# ALIM.net
KiCad netlist of a schematic drawn in EAGLE
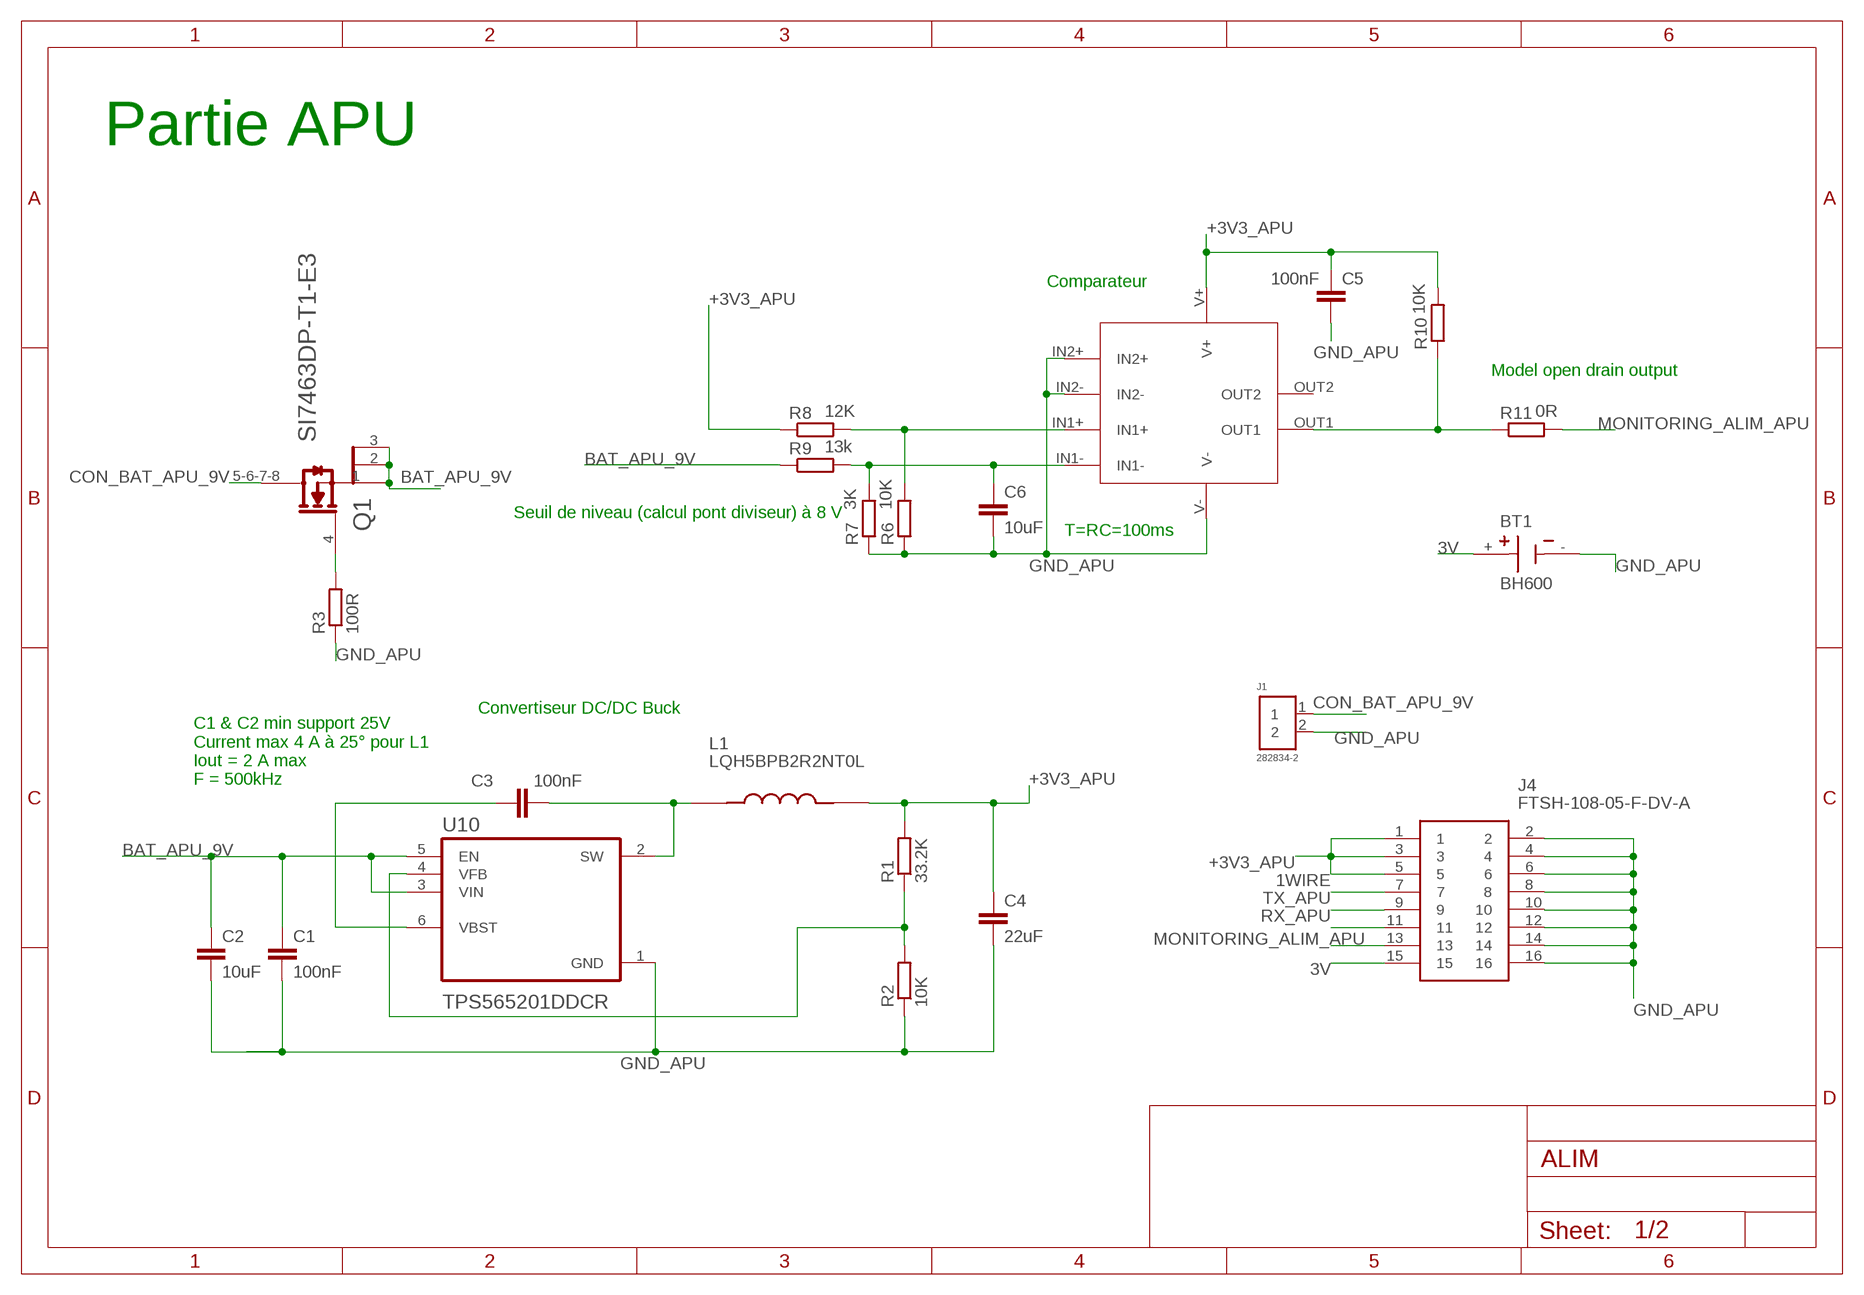
[diagram p0: schematic, sheet 1]
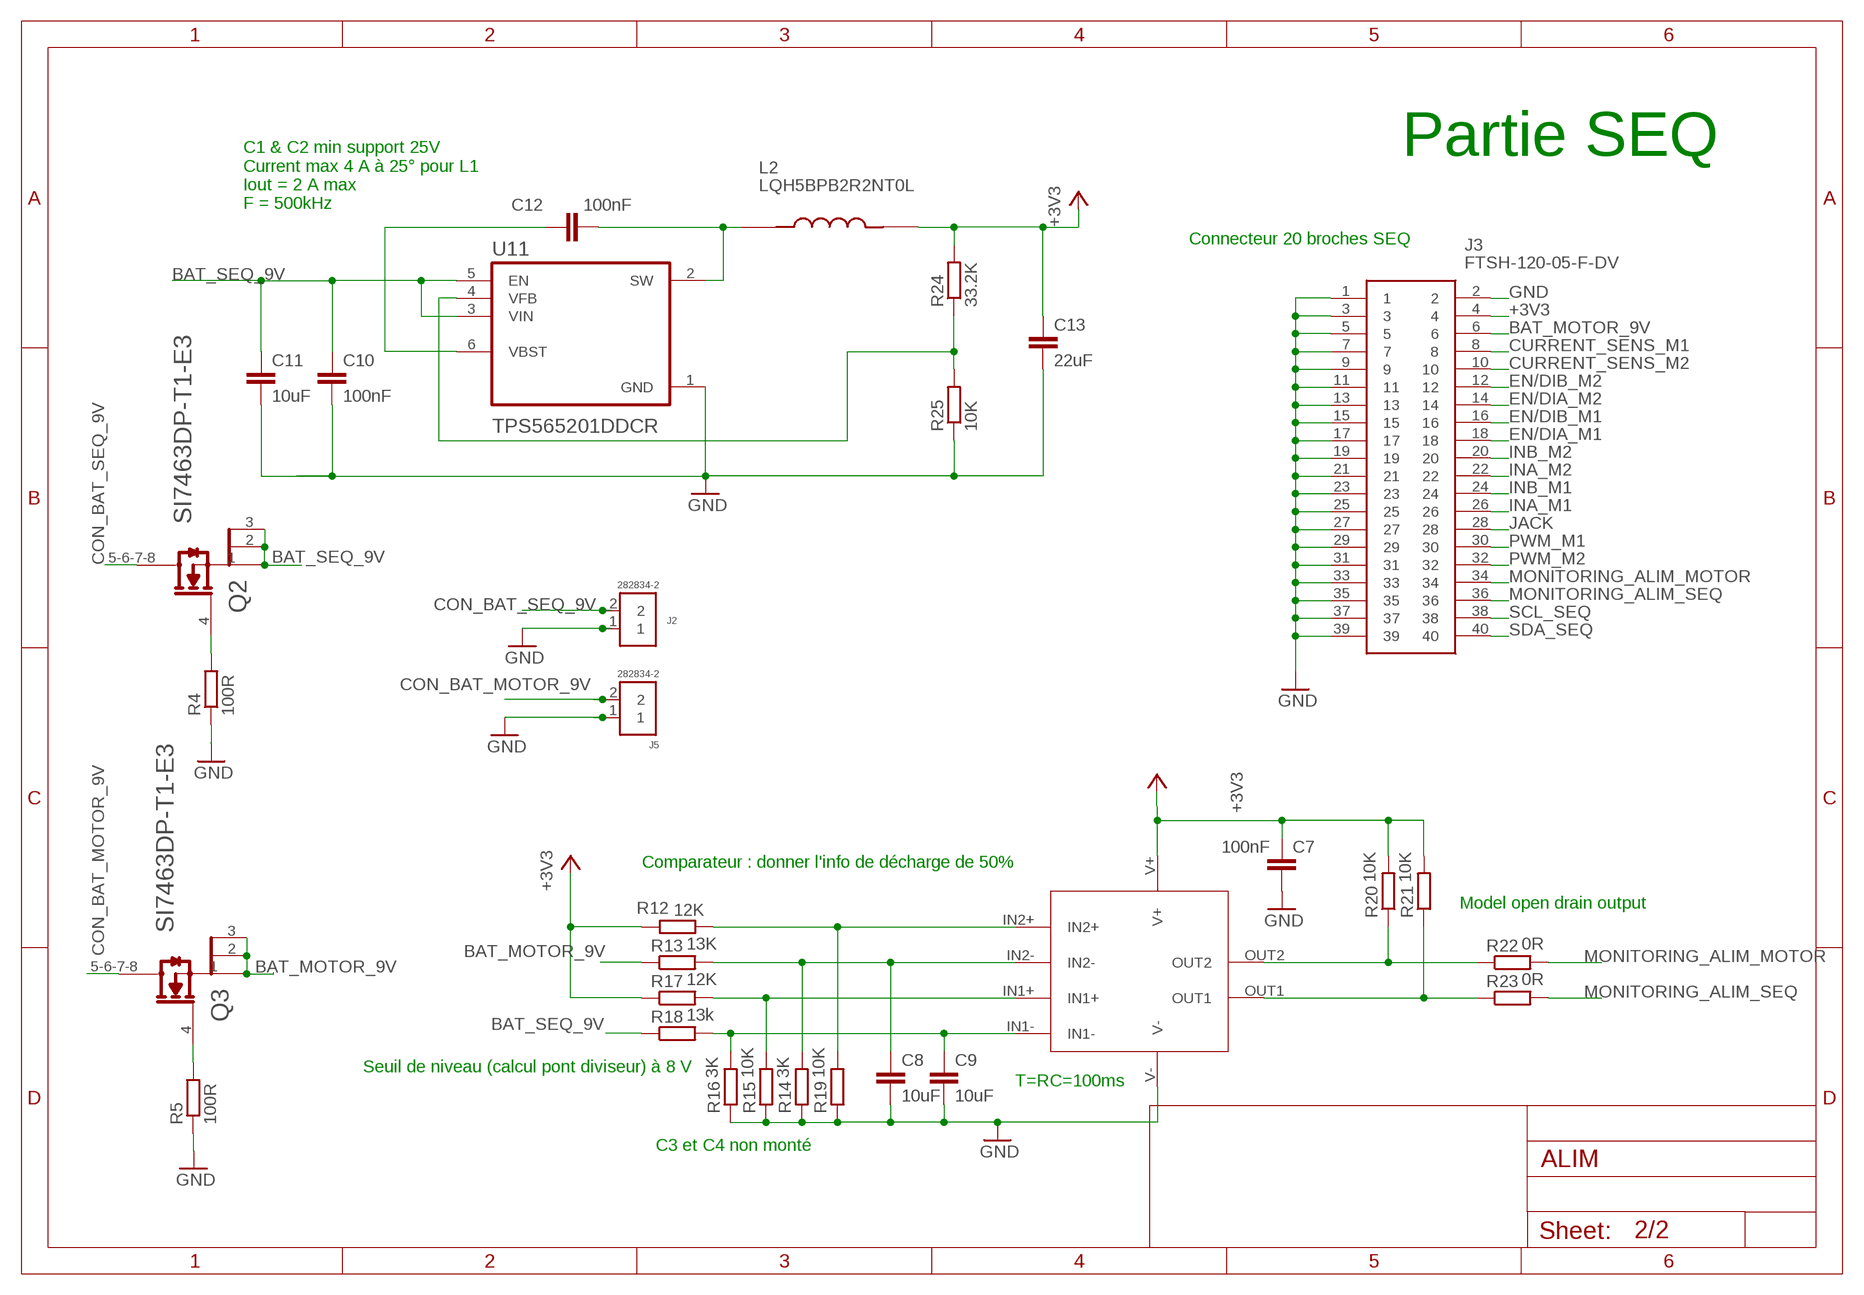
[diagram p1: schematic, sheet 2]

(export (version "E")
  (design (tool "Eeschema 10.0.6"))
  (components
    (comp (ref "BT1")
      (value "BH600")
      (footprint "eagle-import:BAT_BH600")
      (fields (field (name "MF") "MPD (Memory"))
      (libsource (lib "eagle-import") (part "BH600"))
    )
    (comp (ref "C1")
      (value "100nF")
      (footprint "eagle-import:C0805")
      (libsource (lib "eagle-import") (part "C-EUC0805"))
    )
    (comp (ref "C2")
      (value "10uF")
      (footprint "eagle-import:C0805")
      (libsource (lib "eagle-import") (part "C-EUC0805"))
    )
    (comp (ref "C3")
      (value "100nF")
      (footprint "eagle-import:C0805")
      (libsource (lib "eagle-import") (part "C-EUC0805"))
    )
    (comp (ref "C4")
      (value "22uF")
      (footprint "eagle-import:C0805")
      (libsource (lib "eagle-import") (part "C-EUC0805"))
    )
    (comp (ref "C5")
      (value "100nF")
      (footprint "eagle-import:C0805")
      (libsource (lib "eagle-import") (part "C-EUC0805"))
    )
    (comp (ref "C6")
      (value "10uF")
      (footprint "eagle-import:C0805")
      (libsource (lib "eagle-import") (part "C-EUC0805"))
    )
    (comp (ref "J1")
      (value "282834-2")
      (footprint "eagle-import:CONN_282834-2")
      (fields (field (name "MF") "TE Connectivity"))
      (libsource (lib "eagle-import") (part "282834-2"))
    )
    (comp (ref "J4")
      (value "FTSH-108-05-F-DV-A")
      (footprint "eagle-import:FTSH-108-XX-YYY-DV-A")
      (fields (field (name "MOUSER_PART_NUMBER") "200-FTSH10805FDVA"))
      (libsource (lib "eagle-import") (part "FTSH-108-05-F-DV-A"))
    )
    (comp (ref "L1")
      (value "LQH5BPB2R2NT0L")
      (footprint "eagle-import:IND_LQH5BPB2R2NT0L")
      (fields (field (name "MF") "Murata"))
      (libsource (lib "eagle-import") (part "LQH5BPB2R2NT0L"))
    )
    (comp (ref "Q1")
      (value "VISHAY_SI7463DP-T1-E3VISHAY_SI7463DP-T1-E3_0_0")
      (footprint "eagle-import:VISHAY_SI7463DP-T1-E3_0")
      (fields
        (field (name "DIGIKEY_PART_NUMBER") "SI7463DP-T1-E3CT-ND")
        (field (name "MF") "Vishay")
        (field (name "MOUSER_PART_NUMBER") "781-SI7463DP-T1-E3")
      )
      (libsource (lib "eagle-import") (part "VISHAY_SI7463DP-T1-E3VISHAY_SI7463DP-T1-E3_0_0"))
    )
    (comp (ref "R1")
      (value "33.2K")
      (footprint "eagle-import:R0603")
      (libsource (lib "eagle-import") (part "R-EU_R0603"))
    )
    (comp (ref "R2")
      (value "10K")
      (footprint "eagle-import:R0603")
      (libsource (lib "eagle-import") (part "R-EU_R0603"))
    )
    (comp (ref "R3")
      (value "100R")
      (footprint "eagle-import:R0603")
      (libsource (lib "eagle-import") (part "R-EU_R0603"))
    )
    (comp (ref "R6")
      (value "10K")
      (footprint "eagle-import:R0603")
      (libsource (lib "eagle-import") (part "R-EU_R0603"))
    )
    (comp (ref "R7")
      (value "3K")
      (footprint "eagle-import:R0603")
      (libsource (lib "eagle-import") (part "R-EU_R0603"))
    )
    (comp (ref "R8")
      (value "12K")
      (footprint "eagle-import:R0603")
      (libsource (lib "eagle-import") (part "R-EU_R0603"))
    )
    (comp (ref "R9")
      (value "13k")
      (footprint "eagle-import:R0603")
      (libsource (lib "eagle-import") (part "R-EU_R0603"))
    )
    (comp (ref "R10")
      (value "10K")
      (footprint "eagle-import:R0603")
      (libsource (lib "eagle-import") (part "R-EU_R0603"))
    )
    (comp (ref "R11")
      (value "0R")
      (footprint "eagle-import:R0603")
      (libsource (lib "eagle-import") (part "R-EU_R0603"))
    )
    (comp (ref "TLV1")
      (value "TLV9022")
      (footprint "eagle-import:TLV9022")
      (libsource (lib "eagle-import") (part "TLV9022"))
    )
    (comp (ref "U10")
      (value "TPS565201DDCR")
      (footprint "eagle-import:SOT95P280X110-6N")
      (fields (field (name "MF") "Texas Instruments"))
      (libsource (lib "eagle-import") (part "TPS565201DDCR"))
    )
    (comp (ref "C7")
      (value "100nF")
      (footprint "eagle-import:C0805")
      (libsource (lib "eagle-import") (part "C-EUC0805"))
    )
    (comp (ref "C8")
      (value "10uF")
      (footprint "eagle-import:C0805")
      (libsource (lib "eagle-import") (part "C-EUC0805"))
    )
    (comp (ref "C9")
      (value "10uF")
      (footprint "eagle-import:C0805")
      (libsource (lib "eagle-import") (part "C-EUC0805"))
    )
    (comp (ref "C10")
      (value "100nF")
      (footprint "eagle-import:C0805")
      (libsource (lib "eagle-import") (part "C-EUC0805"))
    )
    (comp (ref "C11")
      (value "10uF")
      (footprint "eagle-import:C0805")
      (libsource (lib "eagle-import") (part "C-EUC0805"))
    )
    (comp (ref "C12")
      (value "100nF")
      (footprint "eagle-import:C0805")
      (libsource (lib "eagle-import") (part "C-EUC0805"))
    )
    (comp (ref "C13")
      (value "22uF")
      (footprint "eagle-import:C0805")
      (libsource (lib "eagle-import") (part "C-EUC0805"))
    )
    (comp (ref "J2")
      (value "282834-2")
      (footprint "eagle-import:CONN_282834-2")
      (fields (field (name "MF") "TE Connectivity"))
      (libsource (lib "eagle-import") (part "282834-2"))
    )
    (comp (ref "J3")
      (value "FTSH-120-05-F-DV")
      (footprint "eagle-import:FTSH-120-XX-YYY-DV")
      (libsource (lib "eagle-import") (part "FTSH-120-05-F-DV"))
    )
    (comp (ref "J5")
      (value "282834-2")
      (footprint "eagle-import:CONN_282834-2")
      (fields (field (name "MF") "TE Connectivity"))
      (libsource (lib "eagle-import") (part "282834-2"))
    )
    (comp (ref "L2")
      (value "LQH5BPB2R2NT0L")
      (footprint "eagle-import:IND_LQH5BPB2R2NT0L")
      (fields (field (name "MF") "Murata"))
      (libsource (lib "eagle-import") (part "LQH5BPB2R2NT0L"))
    )
    (comp (ref "Q2")
      (value "VISHAY_SI7463DP-T1-E3VISHAY_SI7463DP-T1-E3_0_0")
      (footprint "eagle-import:VISHAY_SI7463DP-T1-E3_0")
      (fields
        (field (name "DIGIKEY_PART_NUMBER") "SI7463DP-T1-E3CT-ND")
        (field (name "MF") "Vishay")
        (field (name "MOUSER_PART_NUMBER") "781-SI7463DP-T1-E3")
      )
      (libsource (lib "eagle-import") (part "VISHAY_SI7463DP-T1-E3VISHAY_SI7463DP-T1-E3_0_0"))
    )
    (comp (ref "Q3")
      (value "VISHAY_SI7463DP-T1-E3VISHAY_SI7463DP-T1-E3_0_0")
      (footprint "eagle-import:VISHAY_SI7463DP-T1-E3_0")
      (fields
        (field (name "DIGIKEY_PART_NUMBER") "SI7463DP-T1-E3CT-ND")
        (field (name "MF") "Vishay")
        (field (name "MOUSER_PART_NUMBER") "781-SI7463DP-T1-E3")
      )
      (libsource (lib "eagle-import") (part "VISHAY_SI7463DP-T1-E3VISHAY_SI7463DP-T1-E3_0_0"))
    )
    (comp (ref "R4")
      (value "100R")
      (footprint "eagle-import:R0603")
      (libsource (lib "eagle-import") (part "R-EU_R0603"))
    )
    (comp (ref "R5")
      (value "100R")
      (footprint "eagle-import:R0603")
      (libsource (lib "eagle-import") (part "R-EU_R0603"))
    )
    (comp (ref "R12")
      (value "12K")
      (footprint "eagle-import:R0603")
      (libsource (lib "eagle-import") (part "R-EU_R0603"))
    )
    (comp (ref "R13")
      (value "13K")
      (footprint "eagle-import:R0603")
      (libsource (lib "eagle-import") (part "R-EU_R0603"))
    )
    (comp (ref "R14")
      (value "3K")
      (footprint "eagle-import:R0603")
      (libsource (lib "eagle-import") (part "R-EU_R0603"))
    )
    (comp (ref "R15")
      (value "10K")
      (footprint "eagle-import:R0603")
      (libsource (lib "eagle-import") (part "R-EU_R0603"))
    )
    (comp (ref "R16")
      (value "3K")
      (footprint "eagle-import:R0603")
      (libsource (lib "eagle-import") (part "R-EU_R0603"))
    )
    (comp (ref "R17")
      (value "12K")
      (footprint "eagle-import:R0603")
      (libsource (lib "eagle-import") (part "R-EU_R0603"))
    )
    (comp (ref "R18")
      (value "13k")
      (footprint "eagle-import:R0603")
      (libsource (lib "eagle-import") (part "R-EU_R0603"))
    )
    (comp (ref "R19")
      (value "10K")
      (footprint "eagle-import:R0603")
      (libsource (lib "eagle-import") (part "R-EU_R0603"))
    )
    (comp (ref "R20")
      (value "10K")
      (footprint "eagle-import:R0603")
      (libsource (lib "eagle-import") (part "R-EU_R0603"))
    )
    (comp (ref "R21")
      (value "10K")
      (footprint "eagle-import:R0603")
      (libsource (lib "eagle-import") (part "R-EU_R0603"))
    )
    (comp (ref "R22")
      (value "0R")
      (footprint "eagle-import:R0603")
      (libsource (lib "eagle-import") (part "R-EU_R0603"))
    )
    (comp (ref "R23")
      (value "0R")
      (footprint "eagle-import:R0603")
      (libsource (lib "eagle-import") (part "R-EU_R0603"))
    )
    (comp (ref "R24")
      (value "33.2K")
      (footprint "eagle-import:R0603")
      (libsource (lib "eagle-import") (part "R-EU_R0603"))
    )
    (comp (ref "R25")
      (value "10K")
      (footprint "eagle-import:R0603")
      (libsource (lib "eagle-import") (part "R-EU_R0603"))
    )
    (comp (ref "TLV2")
      (value "TLV9022")
      (footprint "eagle-import:TLV9022")
      (libsource (lib "eagle-import") (part "TLV9022"))
    )
    (comp (ref "U11")
      (value "TPS565201DDCR")
      (footprint "eagle-import:SOT95P280X110-6N")
      (fields (field (name "MF") "Texas Instruments"))
      (libsource (lib "eagle-import") (part "TPS565201DDCR"))
    )
  )
  (nets
    (net (code "1") (name "+3V3") (class "Default")
      (node (ref "C13") (pin "1") (pinfunction "1_1") (pintype "passive"))
      (node (ref "C7") (pin "1") (pinfunction "1_1") (pintype "passive"))
      (node (ref "J3") (pin "4") (pinfunction "4_4") (pintype "bidirectional"))
      (node (ref "L2") (pin "2") (pinfunction "2_2") (pintype "passive"))
      (node (ref "R12") (pin "2") (pinfunction "2_2") (pintype "passive"))
      (node (ref "R17") (pin "1") (pinfunction "1_1") (pintype "passive"))
      (node (ref "R20") (pin "2") (pinfunction "2_2") (pintype "passive"))
      (node (ref "R21") (pin "2") (pinfunction "2_2") (pintype "passive"))
      (node (ref "R24") (pin "2") (pinfunction "2_2") (pintype "passive"))
      (node (ref "TLV2") (pin "V+") (pinfunction "V+_V+") (pintype "bidirectional"))
    )
    (net (code "2") (name "+3V3_APU") (class "Default")
      (node (ref "C4") (pin "1") (pinfunction "1_1") (pintype "passive"))
      (node (ref "C5") (pin "1") (pinfunction "1_1") (pintype "passive"))
      (node (ref "J4") (pin "1") (pinfunction "1_1") (pintype "bidirectional"))
      (node (ref "J4") (pin "3") (pinfunction "3_3") (pintype "bidirectional"))
      (node (ref "J4") (pin "5") (pinfunction "5_5") (pintype "bidirectional"))
      (node (ref "L1") (pin "2") (pinfunction "2_2") (pintype "passive"))
      (node (ref "R1") (pin "2") (pinfunction "2_2") (pintype "passive"))
      (node (ref "R10") (pin "2") (pinfunction "2_2") (pintype "passive"))
      (node (ref "R8") (pin "1") (pinfunction "1_1") (pintype "passive"))
      (node (ref "TLV1") (pin "V+") (pinfunction "V+_V+") (pintype "bidirectional"))
    )
    (net (code "3") (name "1WIRE") (class "Default")
      (node (ref "J4") (pin "7") (pinfunction "7_7") (pintype "bidirectional"))
    )
    (net (code "4") (name "3V") (class "Default")
      (node (ref "BT1") (pin "+") (pinfunction "+_+") (pintype "passive"))
      (node (ref "J4") (pin "15") (pinfunction "15_15") (pintype "bidirectional"))
    )
    (net (code "5") (name "BAT_APU_9V") (class "Default")
      (node (ref "C1") (pin "1") (pinfunction "1_1") (pintype "passive"))
      (node (ref "C2") (pin "1") (pinfunction "1_1") (pintype "passive"))
      (node (ref "Q1") (pin "1") (pinfunction "1_S_1") (pintype "passive"))
      (node (ref "Q1") (pin "2") (pinfunction "2_S_2") (pintype "passive"))
      (node (ref "Q1") (pin "3") (pinfunction "3_S_3") (pintype "passive"))
      (node (ref "R9") (pin "1") (pinfunction "1_1") (pintype "passive"))
      (node (ref "U10") (pin "3") (pinfunction "VIN_3") (pintype "input"))
      (node (ref "U10") (pin "5") (pinfunction "EN_5") (pintype "input"))
    )
    (net (code "6") (name "BAT_MOTOR_9V") (class "Default")
      (node (ref "J3") (pin "6") (pinfunction "6_6") (pintype "bidirectional"))
      (node (ref "Q3") (pin "1") (pinfunction "1_S_1") (pintype "passive"))
      (node (ref "Q3") (pin "2") (pinfunction "2_S_2") (pintype "passive"))
      (node (ref "Q3") (pin "3") (pinfunction "3_S_3") (pintype "passive"))
      (node (ref "R13") (pin "1") (pinfunction "1_1") (pintype "passive"))
    )
    (net (code "7") (name "BAT_SEQ_9V") (class "Default")
      (node (ref "C10") (pin "1") (pinfunction "1_1") (pintype "passive"))
      (node (ref "C11") (pin "1") (pinfunction "1_1") (pintype "passive"))
      (node (ref "Q2") (pin "1") (pinfunction "1_S_1") (pintype "passive"))
      (node (ref "Q2") (pin "2") (pinfunction "2_S_2") (pintype "passive"))
      (node (ref "Q2") (pin "3") (pinfunction "3_S_3") (pintype "passive"))
      (node (ref "R18") (pin "1") (pinfunction "1_1") (pintype "passive"))
      (node (ref "U11") (pin "3") (pinfunction "VIN_3") (pintype "input"))
      (node (ref "U11") (pin "5") (pinfunction "EN_5") (pintype "input"))
    )
    (net (code "8") (name "CON_BAT_APU_9V") (class "Default")
      (node (ref "J1") (pin "1") (pinfunction "1_1") (pintype "passive"))
      (node (ref "Q1") (pin "5-6-7-8") (pinfunction "D_5-6-7-8") (pintype "passive"))
    )
    (net (code "9") (name "CON_BAT_MOTOR_9V") (class "Default")
      (node (ref "J5") (pin "2") (pinfunction "2_2") (pintype "passive"))
      (node (ref "Q3") (pin "5-6-7-8") (pinfunction "D_5-6-7-8") (pintype "passive"))
    )
    (net (code "10") (name "CON_BAT_SEQ_9V") (class "Default")
      (node (ref "J2") (pin "2") (pinfunction "2_2") (pintype "passive"))
      (node (ref "Q2") (pin "5-6-7-8") (pinfunction "D_5-6-7-8") (pintype "passive"))
    )
    (net (code "11") (name "CURRENT_SENS_M1") (class "Default")
      (node (ref "J3") (pin "8") (pinfunction "8_8") (pintype "bidirectional"))
    )
    (net (code "12") (name "CURRENT_SENS_M2") (class "Default")
      (node (ref "J3") (pin "10") (pinfunction "10_10") (pintype "bidirectional"))
    )
    (net (code "13") (name "EN{slash}DIA_M1") (class "Default")
      (node (ref "J3") (pin "18") (pinfunction "18_18") (pintype "bidirectional"))
    )
    (net (code "14") (name "EN{slash}DIA_M2") (class "Default")
      (node (ref "J3") (pin "14") (pinfunction "14_14") (pintype "bidirectional"))
    )
    (net (code "15") (name "EN{slash}DIB_M1") (class "Default")
      (node (ref "J3") (pin "16") (pinfunction "16_16") (pintype "bidirectional"))
    )
    (net (code "16") (name "EN{slash}DIB_M2") (class "Default")
      (node (ref "J3") (pin "12") (pinfunction "12_12") (pintype "bidirectional"))
    )
    (net (code "17") (name "GND") (class "Default")
      (node (ref "C10") (pin "2") (pinfunction "2_2") (pintype "passive"))
      (node (ref "C11") (pin "2") (pinfunction "2_2") (pintype "passive"))
      (node (ref "C13") (pin "2") (pinfunction "2_2") (pintype "passive"))
      (node (ref "C7") (pin "2") (pinfunction "2_2") (pintype "passive"))
      (node (ref "C8") (pin "2") (pinfunction "2_2") (pintype "passive"))
      (node (ref "C9") (pin "2") (pinfunction "2_2") (pintype "passive"))
      (node (ref "J2") (pin "1") (pinfunction "1_1") (pintype "passive"))
      (node (ref "J3") (pin "1") (pinfunction "1_1") (pintype "bidirectional"))
      (node (ref "J3") (pin "11") (pinfunction "11_11") (pintype "bidirectional"))
      (node (ref "J3") (pin "13") (pinfunction "13_13") (pintype "bidirectional"))
      (node (ref "J3") (pin "15") (pinfunction "15_15") (pintype "bidirectional"))
      (node (ref "J3") (pin "17") (pinfunction "17_17") (pintype "bidirectional"))
      (node (ref "J3") (pin "19") (pinfunction "19_19") (pintype "bidirectional"))
      (node (ref "J3") (pin "2") (pinfunction "2_2") (pintype "bidirectional"))
      (node (ref "J3") (pin "21") (pinfunction "21_21") (pintype "bidirectional"))
      (node (ref "J3") (pin "23") (pinfunction "23_23") (pintype "bidirectional"))
      (node (ref "J3") (pin "25") (pinfunction "25_25") (pintype "bidirectional"))
      (node (ref "J3") (pin "27") (pinfunction "27_27") (pintype "bidirectional"))
      (node (ref "J3") (pin "29") (pinfunction "29_29") (pintype "bidirectional"))
      (node (ref "J3") (pin "3") (pinfunction "3_3") (pintype "bidirectional"))
      (node (ref "J3") (pin "31") (pinfunction "31_31") (pintype "bidirectional"))
      (node (ref "J3") (pin "33") (pinfunction "33_33") (pintype "bidirectional"))
      (node (ref "J3") (pin "35") (pinfunction "35_35") (pintype "bidirectional"))
      (node (ref "J3") (pin "37") (pinfunction "37_37") (pintype "bidirectional"))
      (node (ref "J3") (pin "39") (pinfunction "39_39") (pintype "bidirectional"))
      (node (ref "J3") (pin "5") (pinfunction "5_5") (pintype "bidirectional"))
      (node (ref "J3") (pin "7") (pinfunction "7_7") (pintype "bidirectional"))
      (node (ref "J3") (pin "9") (pinfunction "9_9") (pintype "bidirectional"))
      (node (ref "J5") (pin "1") (pinfunction "1_1") (pintype "passive"))
      (node (ref "R14") (pin "1") (pinfunction "1_1") (pintype "passive"))
      (node (ref "R15") (pin "1") (pinfunction "1_1") (pintype "passive"))
      (node (ref "R16") (pin "1") (pinfunction "1_1") (pintype "passive"))
      (node (ref "R19") (pin "1") (pinfunction "1_1") (pintype "passive"))
      (node (ref "R25") (pin "1") (pinfunction "1_1") (pintype "passive"))
      (node (ref "R4") (pin "1") (pinfunction "1_1") (pintype "passive"))
      (node (ref "R5") (pin "1") (pinfunction "1_1") (pintype "passive"))
      (node (ref "TLV2") (pin "V-") (pinfunction "V-_V-") (pintype "bidirectional"))
      (node (ref "U11") (pin "1") (pinfunction "GND_1") (pintype "power_in"))
    )
    (net (code "18") (name "GND_APU") (class "Default")
      (node (ref "BT1") (pin "-") (pinfunction "-_-") (pintype "passive"))
      (node (ref "C1") (pin "2") (pinfunction "2_2") (pintype "passive"))
      (node (ref "C2") (pin "2") (pinfunction "2_2") (pintype "passive"))
      (node (ref "C4") (pin "2") (pinfunction "2_2") (pintype "passive"))
      (node (ref "C5") (pin "2") (pinfunction "2_2") (pintype "passive"))
      (node (ref "C6") (pin "2") (pinfunction "2_2") (pintype "passive"))
      (node (ref "J1") (pin "2") (pinfunction "2_2") (pintype "passive"))
      (node (ref "J4") (pin "10") (pinfunction "10_10") (pintype "bidirectional"))
      (node (ref "J4") (pin "12") (pinfunction "12_12") (pintype "bidirectional"))
      (node (ref "J4") (pin "14") (pinfunction "14_14") (pintype "bidirectional"))
      (node (ref "J4") (pin "16") (pinfunction "16_16") (pintype "bidirectional"))
      (node (ref "J4") (pin "2") (pinfunction "2_2") (pintype "bidirectional"))
      (node (ref "J4") (pin "4") (pinfunction "4_4") (pintype "bidirectional"))
      (node (ref "J4") (pin "6") (pinfunction "6_6") (pintype "bidirectional"))
      (node (ref "J4") (pin "8") (pinfunction "8_8") (pintype "bidirectional"))
      (node (ref "R2") (pin "1") (pinfunction "1_1") (pintype "passive"))
      (node (ref "R3") (pin "1") (pinfunction "1_1") (pintype "passive"))
      (node (ref "R6") (pin "1") (pinfunction "1_1") (pintype "passive"))
      (node (ref "R7") (pin "1") (pinfunction "1_1") (pintype "passive"))
      (node (ref "TLV1") (pin "IN2+") (pinfunction "IN2+_IN2+") (pintype "bidirectional"))
      (node (ref "TLV1") (pin "IN2-") (pinfunction "IN2-_IN2-") (pintype "bidirectional"))
      (node (ref "TLV1") (pin "V-") (pinfunction "V-_V-") (pintype "bidirectional"))
      (node (ref "U10") (pin "1") (pinfunction "GND_1") (pintype "power_in"))
    )
    (net (code "19") (name "INA_M1") (class "Default")
      (node (ref "J3") (pin "26") (pinfunction "26_26") (pintype "bidirectional"))
    )
    (net (code "20") (name "INA_M2") (class "Default")
      (node (ref "J3") (pin "22") (pinfunction "22_22") (pintype "bidirectional"))
    )
    (net (code "21") (name "INB_M1") (class "Default")
      (node (ref "J3") (pin "24") (pinfunction "24_24") (pintype "bidirectional"))
    )
    (net (code "22") (name "INB_M2") (class "Default")
      (node (ref "J3") (pin "20") (pinfunction "20_20") (pintype "bidirectional"))
    )
    (net (code "23") (name "JACK") (class "Default")
      (node (ref "J3") (pin "28") (pinfunction "28_28") (pintype "bidirectional"))
    )
    (net (code "24") (name "MONITORING_ALIM_APU") (class "Default")
      (node (ref "J4") (pin "13") (pinfunction "13_13") (pintype "bidirectional"))
      (node (ref "R11") (pin "2") (pinfunction "2_2") (pintype "passive"))
    )
    (net (code "25") (name "MONITORING_ALIM_MOTOR") (class "Default")
      (node (ref "J3") (pin "34") (pinfunction "34_34") (pintype "bidirectional"))
      (node (ref "R22") (pin "2") (pinfunction "2_2") (pintype "passive"))
    )
    (net (code "26") (name "MONITORING_ALIM_SEQ") (class "Default")
      (node (ref "J3") (pin "36") (pinfunction "36_36") (pintype "bidirectional"))
      (node (ref "R23") (pin "2") (pinfunction "2_2") (pintype "passive"))
    )
    (net (code "27") (name "Net-(C6-Pad1)") (class "Default")
      (node (ref "C6") (pin "1") (pinfunction "1_1") (pintype "passive"))
      (node (ref "R7") (pin "2") (pinfunction "2_2") (pintype "passive"))
      (node (ref "R9") (pin "2") (pinfunction "2_2") (pintype "passive"))
      (node (ref "TLV1") (pin "IN1-") (pinfunction "IN1-_IN1-") (pintype "bidirectional"))
    )
    (net (code "28") (name "Net-(C8-Pad1)") (class "Default")
      (node (ref "C8") (pin "1") (pinfunction "1_1") (pintype "passive"))
      (node (ref "R13") (pin "2") (pinfunction "2_2") (pintype "passive"))
      (node (ref "R14") (pin "2") (pinfunction "2_2") (pintype "passive"))
      (node (ref "TLV2") (pin "IN2-") (pinfunction "IN2-_IN2-") (pintype "bidirectional"))
    )
    (net (code "29") (name "Net-(C9-Pad1)") (class "Default")
      (node (ref "C9") (pin "1") (pinfunction "1_1") (pintype "passive"))
      (node (ref "R16") (pin "2") (pinfunction "2_2") (pintype "passive"))
      (node (ref "R18") (pin "2") (pinfunction "2_2") (pintype "passive"))
      (node (ref "TLV2") (pin "IN1-") (pinfunction "IN1-_IN1-") (pintype "bidirectional"))
    )
    (net (code "30") (name "Net-(Q1-G)") (class "Default")
      (node (ref "Q1") (pin "4") (pinfunction "G_4") (pintype "passive"))
      (node (ref "R3") (pin "2") (pinfunction "2_2") (pintype "passive"))
    )
    (net (code "31") (name "Net-(Q2-G)") (class "Default")
      (node (ref "Q2") (pin "4") (pinfunction "G_4") (pintype "passive"))
      (node (ref "R4") (pin "2") (pinfunction "2_2") (pintype "passive"))
    )
    (net (code "32") (name "Net-(Q3-G)") (class "Default")
      (node (ref "Q3") (pin "4") (pinfunction "G_4") (pintype "passive"))
      (node (ref "R5") (pin "2") (pinfunction "2_2") (pintype "passive"))
    )
    (net (code "33") (name "Net-(R6-Pad2)") (class "Default")
      (node (ref "R6") (pin "2") (pinfunction "2_2") (pintype "passive"))
      (node (ref "R8") (pin "2") (pinfunction "2_2") (pintype "passive"))
      (node (ref "TLV1") (pin "IN1+") (pinfunction "IN1+_IN1+") (pintype "bidirectional"))
    )
    (net (code "34") (name "Net-(R10-Pad1)") (class "Default")
      (node (ref "R10") (pin "1") (pinfunction "1_1") (pintype "passive"))
      (node (ref "R11") (pin "1") (pinfunction "1_1") (pintype "passive"))
      (node (ref "TLV1") (pin "OUT1") (pinfunction "OUT1_OUT1") (pintype "bidirectional"))
    )
    (net (code "35") (name "Net-(R12-Pad1)") (class "Default")
      (node (ref "R12") (pin "1") (pinfunction "1_1") (pintype "passive"))
      (node (ref "R19") (pin "2") (pinfunction "2_2") (pintype "passive"))
      (node (ref "TLV2") (pin "IN2+") (pinfunction "IN2+_IN2+") (pintype "bidirectional"))
    )
    (net (code "36") (name "Net-(R15-Pad2)") (class "Default")
      (node (ref "R15") (pin "2") (pinfunction "2_2") (pintype "passive"))
      (node (ref "R17") (pin "2") (pinfunction "2_2") (pintype "passive"))
      (node (ref "TLV2") (pin "IN1+") (pinfunction "IN1+_IN1+") (pintype "bidirectional"))
    )
    (net (code "37") (name "Net-(R20-Pad1)") (class "Default")
      (node (ref "R20") (pin "1") (pinfunction "1_1") (pintype "passive"))
      (node (ref "R22") (pin "1") (pinfunction "1_1") (pintype "passive"))
      (node (ref "TLV2") (pin "OUT2") (pinfunction "OUT2_OUT2") (pintype "bidirectional"))
    )
    (net (code "38") (name "Net-(R21-Pad1)") (class "Default")
      (node (ref "R21") (pin "1") (pinfunction "1_1") (pintype "passive"))
      (node (ref "R23") (pin "1") (pinfunction "1_1") (pintype "passive"))
      (node (ref "TLV2") (pin "OUT1") (pinfunction "OUT1_OUT1") (pintype "bidirectional"))
    )
    (net (code "39") (name "Net-(U10-SW)") (class "Default")
      (node (ref "C3") (pin "2") (pinfunction "2_2") (pintype "passive"))
      (node (ref "L1") (pin "1") (pinfunction "1_1") (pintype "passive"))
      (node (ref "U10") (pin "2") (pinfunction "SW_2") (pintype "output"))
    )
    (net (code "40") (name "Net-(U10-VBST)") (class "Default")
      (node (ref "C3") (pin "1") (pinfunction "1_1") (pintype "passive"))
      (node (ref "U10") (pin "6") (pinfunction "VBST_6") (pintype "bidirectional"))
    )
    (net (code "41") (name "Net-(U10-VFB)") (class "Default")
      (node (ref "R1") (pin "1") (pinfunction "1_1") (pintype "passive"))
      (node (ref "R2") (pin "2") (pinfunction "2_2") (pintype "passive"))
      (node (ref "U10") (pin "4") (pinfunction "VFB_4") (pintype "input"))
    )
    (net (code "42") (name "Net-(U11-SW)") (class "Default")
      (node (ref "C12") (pin "2") (pinfunction "2_2") (pintype "passive"))
      (node (ref "L2") (pin "1") (pinfunction "1_1") (pintype "passive"))
      (node (ref "U11") (pin "2") (pinfunction "SW_2") (pintype "output"))
    )
    (net (code "43") (name "Net-(U11-VBST)") (class "Default")
      (node (ref "C12") (pin "1") (pinfunction "1_1") (pintype "passive"))
      (node (ref "U11") (pin "6") (pinfunction "VBST_6") (pintype "bidirectional"))
    )
    (net (code "44") (name "Net-(U11-VFB)") (class "Default")
      (node (ref "R24") (pin "1") (pinfunction "1_1") (pintype "passive"))
      (node (ref "R25") (pin "2") (pinfunction "2_2") (pintype "passive"))
      (node (ref "U11") (pin "4") (pinfunction "VFB_4") (pintype "input"))
    )
    (net (code "45") (name "PWM_M1") (class "Default")
      (node (ref "J3") (pin "30") (pinfunction "30_30") (pintype "bidirectional"))
    )
    (net (code "46") (name "PWM_M2") (class "Default")
      (node (ref "J3") (pin "32") (pinfunction "32_32") (pintype "bidirectional"))
    )
    (net (code "47") (name "RX_APU") (class "Default")
      (node (ref "J4") (pin "11") (pinfunction "11_11") (pintype "bidirectional"))
    )
    (net (code "48") (name "SCL_SEQ") (class "Default")
      (node (ref "J3") (pin "38") (pinfunction "38_38") (pintype "bidirectional"))
    )
    (net (code "49") (name "SDA_SEQ") (class "Default")
      (node (ref "J3") (pin "40") (pinfunction "40_40") (pintype "bidirectional"))
    )
    (net (code "50") (name "TX_APU") (class "Default")
      (node (ref "J4") (pin "9") (pinfunction "9_9") (pintype "bidirectional"))
    )
    (net (code "51") (name "unconnected-(TLV1-PadOUT2)") (class "Default")
      (node (ref "TLV1") (pin "OUT2") (pinfunction "OUT2_OUT2") (pintype "bidirectional"))
    )
  )
)
